# D1MPROTO.net
KiCad netlist of a schematic drawn in EAGLE
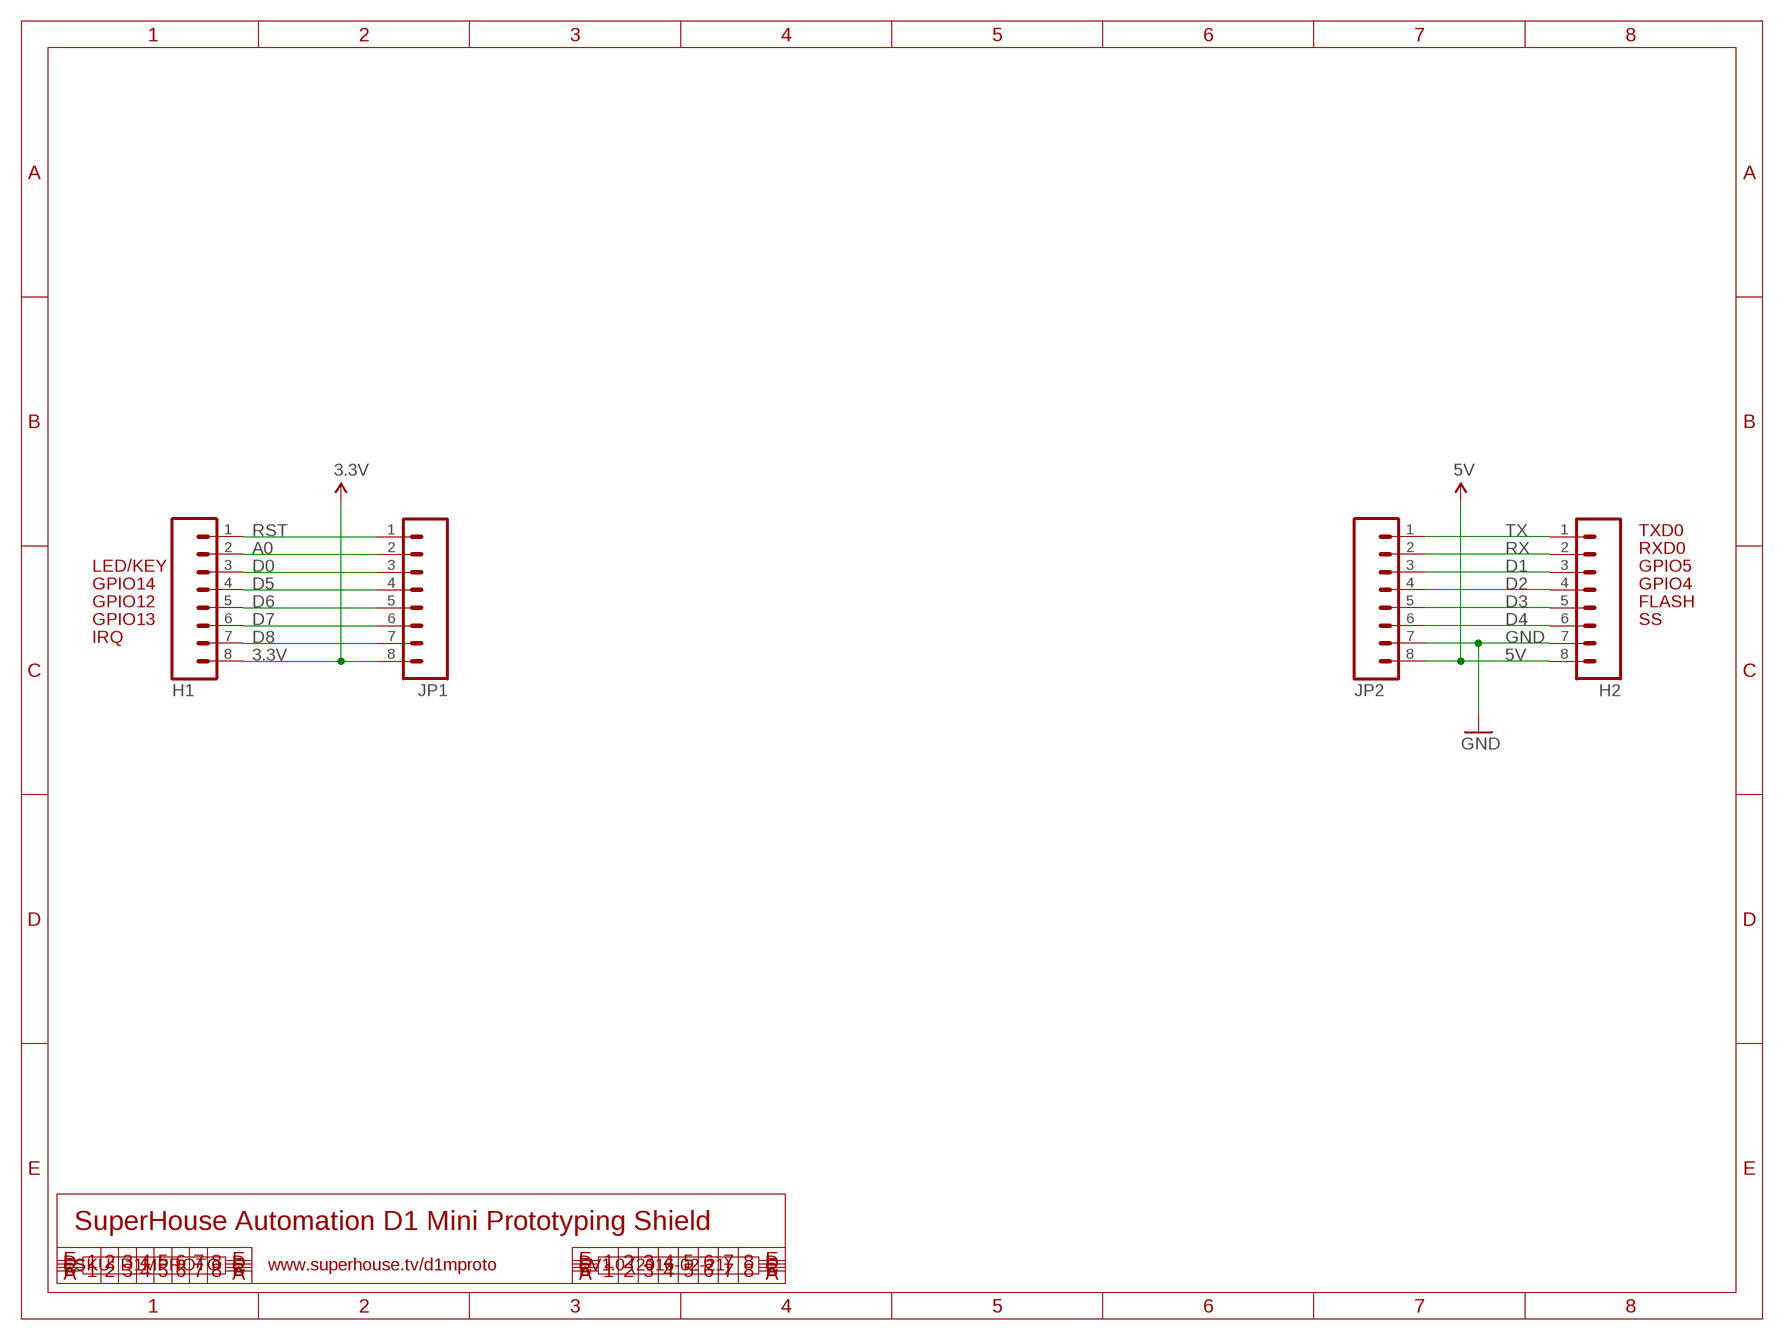
[diagram p0: schematic, sheet 1]

(export (version "E")
  (design (tool "Eeschema 10.0.6"))
  (components
    (comp (ref "H1")
      (value "M08")
      (footprint "eagle-import:1X08")
      (libsource (lib "eagle-import") (part "M08"))
    )
    (comp (ref "H2")
      (value "M08")
      (footprint "eagle-import:1X08")
      (libsource (lib "eagle-import") (part "M08"))
    )
    (comp (ref "JP1")
      (value "M08")
      (footprint "eagle-import:1X08")
      (libsource (lib "eagle-import") (part "M08"))
    )
    (comp (ref "JP2")
      (value "M08")
      (footprint "eagle-import:1X08")
      (libsource (lib "eagle-import") (part "M08"))
    )
  )
  (nets
    (net (code "1") (name "/A0") (class "Default")
      (node (ref "H1") (pin "2") (pinfunction "2_2") (pintype "passive"))
      (node (ref "JP1") (pin "2") (pinfunction "2_2") (pintype "passive"))
    )
    (net (code "2") (name "/D0") (class "Default")
      (node (ref "H1") (pin "3") (pinfunction "3_3") (pintype "passive"))
      (node (ref "JP1") (pin "3") (pinfunction "3_3") (pintype "passive"))
    )
    (net (code "3") (name "/D1") (class "Default")
      (node (ref "H2") (pin "3") (pinfunction "3_3") (pintype "passive"))
      (node (ref "JP2") (pin "3") (pinfunction "3_3") (pintype "passive"))
    )
    (net (code "4") (name "/D2") (class "Default")
      (node (ref "H2") (pin "4") (pinfunction "4_4") (pintype "passive"))
      (node (ref "JP2") (pin "4") (pinfunction "4_4") (pintype "passive"))
    )
    (net (code "5") (name "/D3") (class "Default")
      (node (ref "H2") (pin "5") (pinfunction "5_5") (pintype "passive"))
      (node (ref "JP2") (pin "5") (pinfunction "5_5") (pintype "passive"))
    )
    (net (code "6") (name "/D4") (class "Default")
      (node (ref "H2") (pin "6") (pinfunction "6_6") (pintype "passive"))
      (node (ref "JP2") (pin "6") (pinfunction "6_6") (pintype "passive"))
    )
    (net (code "7") (name "/D5") (class "Default")
      (node (ref "H1") (pin "4") (pinfunction "4_4") (pintype "passive"))
      (node (ref "JP1") (pin "4") (pinfunction "4_4") (pintype "passive"))
    )
    (net (code "8") (name "/D6") (class "Default")
      (node (ref "H1") (pin "5") (pinfunction "5_5") (pintype "passive"))
      (node (ref "JP1") (pin "5") (pinfunction "5_5") (pintype "passive"))
    )
    (net (code "9") (name "/D7") (class "Default")
      (node (ref "H1") (pin "6") (pinfunction "6_6") (pintype "passive"))
      (node (ref "JP1") (pin "6") (pinfunction "6_6") (pintype "passive"))
    )
    (net (code "10") (name "/D8") (class "Default")
      (node (ref "H1") (pin "7") (pinfunction "7_7") (pintype "passive"))
      (node (ref "JP1") (pin "7") (pinfunction "7_7") (pintype "passive"))
    )
    (net (code "11") (name "/RST") (class "Default")
      (node (ref "H1") (pin "1") (pinfunction "1_1") (pintype "passive"))
      (node (ref "JP1") (pin "1") (pinfunction "1_1") (pintype "passive"))
    )
    (net (code "12") (name "/RX") (class "Default")
      (node (ref "H2") (pin "2") (pinfunction "2_2") (pintype "passive"))
      (node (ref "JP2") (pin "2") (pinfunction "2_2") (pintype "passive"))
    )
    (net (code "13") (name "/TX") (class "Default")
      (node (ref "H2") (pin "1") (pinfunction "1_1") (pintype "passive"))
      (node (ref "JP2") (pin "1") (pinfunction "1_1") (pintype "passive"))
    )
    (net (code "14") (name "3.3V") (class "Default")
      (node (ref "H1") (pin "8") (pinfunction "8_8") (pintype "passive"))
      (node (ref "JP1") (pin "8") (pinfunction "8_8") (pintype "passive"))
    )
    (net (code "15") (name "5V") (class "Default")
      (node (ref "H2") (pin "8") (pinfunction "8_8") (pintype "passive"))
      (node (ref "JP2") (pin "8") (pinfunction "8_8") (pintype "passive"))
    )
    (net (code "16") (name "GND") (class "Default")
      (node (ref "H2") (pin "7") (pinfunction "7_7") (pintype "passive"))
      (node (ref "JP2") (pin "7") (pinfunction "7_7") (pintype "passive"))
    )
  )
)
